# design.net
KiCad netlist of a schematic drawn in Altium Designer
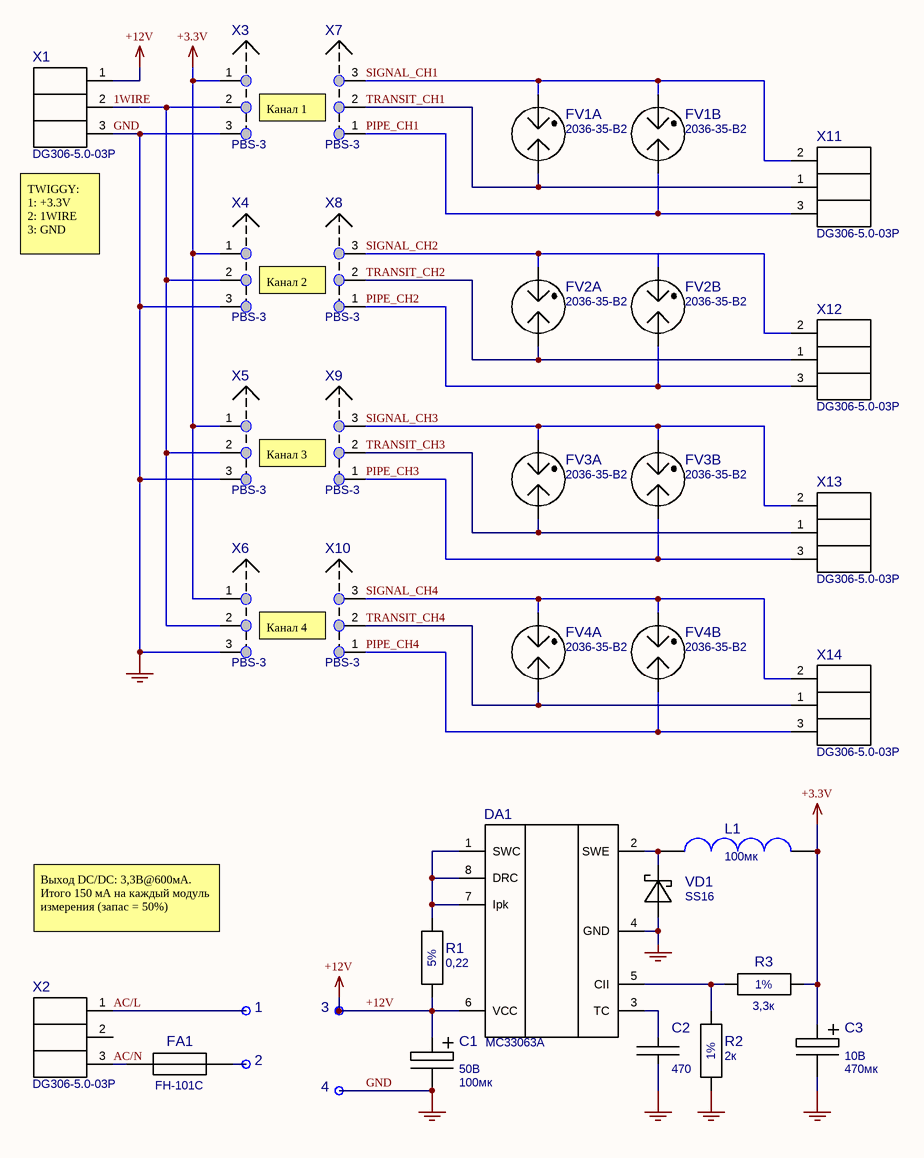
[diagram p0: Модуль соединений.SchDoc]

(export (version "E")
  (design (tool "Eeschema 10.0.6"))
  (components
    (comp (ref "1")
      (value "Plated Hole")
      (footprint "c150h100")
      (description "Single Terminal Socket")
      (fields (field (name "PART NUMBER") "PLATED_HOLE1.0_PAD1.5") (field (name "AUTHOR") "CERN DEM JLC"))
      (libsource (lib "Eletro-mechanical") (part "Single Terminal Socket"))
    )
    (comp (ref "2")
      (value "Plated Hole")
      (footprint "c150h100")
      (description "Single Terminal Socket")
      (fields (field (name "PART NUMBER") "PLATED_HOLE1.0_PAD1.5") (field (name "AUTHOR") "CERN DEM JLC"))
      (libsource (lib "Eletro-mechanical") (part "Single Terminal Socket"))
    )
    (comp (ref "3")
      (value "Plated Hole")
      (footprint "c150h100")
      (description "Single Terminal Socket")
      (fields (field (name "PART NUMBER") "PLATED_HOLE1.0_PAD1.5") (field (name "AUTHOR") "CERN DEM JLC"))
      (libsource (lib "Eletro-mechanical") (part "Single Terminal Socket"))
    )
    (comp (ref "4")
      (value "Plated Hole")
      (footprint "c150h100")
      (description "Single Terminal Socket")
      (fields (field (name "PART NUMBER") "PLATED_HOLE1.0_PAD1.5") (field (name "AUTHOR") "CERN DEM JLC"))
      (libsource (lib "Eletro-mechanical") (part "Single Terminal Socket"))
    )
    (comp (ref "C1")
      (value "100мк")
      (footprint "HITANO D08,0 H12,0 P03,5")
      (description "ECR-50 В-100 мкФ±20 %")
      (fields (field (name "VOLTAGE") "50В"))
      (libsource (lib "Калибратор") (part "ECR-50 В-100 мкФ±20 %"))
    )
    (comp (ref "C2")
      (value "470")
      (footprint "CAPC1608L")
      (description "NP0 0603-50 В-470 пФ±5 %")
      (libsource (lib "Калибратор") (part "NP0 0603-50 В-470 пФ±5 %"))
    )
    (comp (ref "C3")
      (value "470мк")
      (footprint "HITANO D08,0 H12,0 P03,5")
      (description "ECR-10 В-470 мкФ±20 %")
      (fields (field (name "VOLTAGE") "10В"))
      (libsource (lib "Калибратор") (part "ECR-10 В-470 мкФ±20 %"))
    )
    (comp (ref "DA1")
      (value "MC33063A")
      (footprint "SO-08 (150MIL)")
      (libsource (lib "Калибратор") (part "MC33063A"))
    )
    (comp (ref "FA1")
      (value "FH-101C")
      (footprint "FH-101")
      (description "FH-101")
      (libsource (lib "КОТ-С") (part "FH-101C"))
    )
    (comp (ref "FV1")
      (value "2036-35-B2")
      (footprint "2036-35-B2")
      (libsource (lib "КОТ-С") (part "2036-35-B2"))
    )
    (comp (ref "FV2")
      (value "2036-35-B2")
      (footprint "2036-35-B2")
      (libsource (lib "") (part "2036-35-B2_1"))
    )
    (comp (ref "FV3")
      (value "2036-35-B2")
      (footprint "2036-35-B2")
      (libsource (lib "") (part "2036-35-B2_1"))
    )
    (comp (ref "FV4")
      (value "2036-35-B2")
      (footprint "2036-35-B2")
      (libsource (lib "") (part "2036-35-B2_1"))
    )
    (comp (ref "L1")
      (value "100мк")
      (footprint "SDR1006")
      (description "SDR1006-101KL 100 мкГн")
      (fields
        (field (name "MANUFACTURER PART NUMBER") "SDR1006-101KL")
        (field (name "MANUFACTURER") "Bourns Inc.")
      )
      (libsource (lib "КОТ-С") (part "SDR1006-101KL 100 мкГн"))
    )
    (comp (ref "R1")
      (value "0,22")
      (footprint "RESC1608L")
      (description "0603 0,22 Ом±5 %")
      (libsource (lib "КОТ-С") (part "0603 0,22 Ом±5 %"))
    )
    (comp (ref "R2")
      (value "2к")
      (footprint "RESC1608L")
      (description "0603 10 кОм±1 %")
      (libsource (lib "КОТ-С") (part "0603 10 кОм±1 %"))
    )
    (comp (ref "R3")
      (value "3,3к")
      (footprint "RESC1608L")
      (description "0603 16 кОм±1 %")
      (libsource (lib "КОТ-С") (part "0603 16 кОм±1 %"))
    )
    (comp (ref "VD1") (value "SS16") (footprint "DO-214AC+") (libsource (lib "Калибратор") (part "SS16")))
    (comp (ref "X1")
      (value "DG306-5.0-03P")
      (footprint "DG306-5.0-03P")
      (libsource (lib "") (part "DG306-5.0-03P_1"))
    )
    (comp (ref "X2")
      (value "DG306-5.0-03P")
      (footprint "DG306-5.0-03P")
      (libsource (lib "") (part "DG306-5.0-03P_1"))
    )
    (comp (ref "X3") (value "PBS-3") (footprint "PBS-3") (libsource (lib "") (part "PBS-3_1")))
    (comp (ref "X4") (value "PBS-3") (footprint "PBS-3") (libsource (lib "") (part "PBS-3_1")))
    (comp (ref "X5") (value "PBS-3") (footprint "PBS-3") (libsource (lib "") (part "PBS-3_1")))
    (comp (ref "X6") (value "PBS-3") (footprint "PBS-3") (libsource (lib "") (part "PBS-3_1")))
    (comp (ref "X7") (value "PBS-3") (footprint "PBS-3") (libsource (lib "КОТ-С") (part "PBS-3")))
    (comp (ref "X8") (value "PBS-3") (footprint "PBS-3") (libsource (lib "КОТ-С") (part "PBS-3")))
    (comp (ref "X9") (value "PBS-3") (footprint "PBS-3") (libsource (lib "КОТ-С") (part "PBS-3")))
    (comp (ref "X10") (value "PBS-3") (footprint "PBS-3") (libsource (lib "КОТ-С") (part "PBS-3")))
    (comp (ref "X11")
      (value "DG306-5.0-03P")
      (footprint "DG306-5.0-03P")
      (libsource (lib "КОТ-С") (part "DG306-5.0-03P"))
    )
    (comp (ref "X12")
      (value "DG306-5.0-03P")
      (footprint "DG306-5.0-03P")
      (libsource (lib "КОТ-С") (part "DG306-5.0-03P"))
    )
    (comp (ref "X13")
      (value "DG306-5.0-03P")
      (footprint "DG306-5.0-03P")
      (libsource (lib "КОТ-С") (part "DG306-5.0-03P"))
    )
    (comp (ref "X14")
      (value "DG306-5.0-03P")
      (footprint "DG306-5.0-03P")
      (libsource (lib "КОТ-С") (part "DG306-5.0-03P"))
    )
  )
  (nets
    (net (code "1") (name "+3.3V") (class "Default")
      (node (ref "C3") (pin "1") (pintype "passive"))
      (node (ref "L1") (pin "2") (pintype "passive"))
      (node (ref "R3") (pin "2") (pintype "passive"))
      (node (ref "X3") (pin "1") (pintype "passive"))
      (node (ref "X4") (pin "1") (pintype "passive"))
      (node (ref "X5") (pin "1") (pintype "passive"))
      (node (ref "X6") (pin "1") (pintype "passive"))
    )
    (net (code "2") (name "+12V") (class "Default")
      (node (ref "3") (pin "1") (pinfunction "1_1") (pintype "bidirectional"))
      (node (ref "C1") (pin "1") (pintype "passive"))
      (node (ref "DA1") (pin "6") (pinfunction "VCC_6") (pintype "passive"))
      (node (ref "R1") (pin "1") (pintype "passive"))
      (node (ref "X1") (pin "1") (pintype "passive"))
    )
    (net (code "3") (name "/1WIRE") (class "Default")
      (node (ref "X1") (pin "2") (pintype "passive"))
      (node (ref "X3") (pin "2") (pintype "passive"))
      (node (ref "X4") (pin "2") (pintype "passive"))
      (node (ref "X5") (pin "2") (pintype "passive"))
      (node (ref "X6") (pin "2") (pintype "passive"))
    )
    (net (code "4") (name "/AC{slash}L") (class "Default")
      (node (ref "1") (pin "1") (pinfunction "1_1") (pintype "bidirectional"))
      (node (ref "X2") (pin "1") (pintype "passive"))
    )
    (net (code "5") (name "/AC{slash}N") (class "Default")
      (node (ref "FA1") (pin "1") (pintype "passive"))
      (node (ref "X2") (pin "3") (pintype "passive"))
    )
    (net (code "6") (name "/PIPE_CH1") (class "Default")
      (node (ref "FV1") (pin "3") (pintype "passive"))
      (node (ref "X11") (pin "3") (pintype "passive"))
      (node (ref "X7") (pin "1") (pintype "passive"))
    )
    (net (code "7") (name "/PIPE_CH2") (class "Default")
      (node (ref "FV2") (pin "3") (pintype "passive"))
      (node (ref "X12") (pin "3") (pintype "passive"))
      (node (ref "X8") (pin "1") (pintype "passive"))
    )
    (net (code "8") (name "/PIPE_CH3") (class "Default")
      (node (ref "FV3") (pin "3") (pintype "passive"))
      (node (ref "X13") (pin "3") (pintype "passive"))
      (node (ref "X9") (pin "1") (pintype "passive"))
    )
    (net (code "9") (name "/PIPE_CH4") (class "Default")
      (node (ref "FV4") (pin "3") (pintype "passive"))
      (node (ref "X10") (pin "1") (pintype "passive"))
      (node (ref "X14") (pin "3") (pintype "passive"))
    )
    (net (code "10") (name "/SIGNAL_CH1") (class "Default")
      (node (ref "FV1") (pin "2") (pintype "passive"))
      (node (ref "X11") (pin "2") (pintype "passive"))
      (node (ref "X7") (pin "3") (pintype "passive"))
    )
    (net (code "11") (name "/SIGNAL_CH2") (class "Default")
      (node (ref "FV2") (pin "2") (pintype "passive"))
      (node (ref "X12") (pin "2") (pintype "passive"))
      (node (ref "X8") (pin "3") (pintype "passive"))
    )
    (net (code "12") (name "/SIGNAL_CH3") (class "Default")
      (node (ref "FV3") (pin "2") (pintype "passive"))
      (node (ref "X13") (pin "2") (pintype "passive"))
      (node (ref "X9") (pin "3") (pintype "passive"))
    )
    (net (code "13") (name "/SIGNAL_CH4") (class "Default")
      (node (ref "FV4") (pin "2") (pintype "passive"))
      (node (ref "X10") (pin "3") (pintype "passive"))
      (node (ref "X14") (pin "2") (pintype "passive"))
    )
    (net (code "14") (name "/TRANSIT_CH1") (class "Default")
      (node (ref "FV1") (pin "1") (pintype "passive"))
      (node (ref "X11") (pin "1") (pintype "passive"))
      (node (ref "X7") (pin "2") (pintype "passive"))
    )
    (net (code "15") (name "/TRANSIT_CH2") (class "Default")
      (node (ref "FV2") (pin "1") (pintype "passive"))
      (node (ref "X12") (pin "1") (pintype "passive"))
      (node (ref "X8") (pin "2") (pintype "passive"))
    )
    (net (code "16") (name "/TRANSIT_CH3") (class "Default")
      (node (ref "FV3") (pin "1") (pintype "passive"))
      (node (ref "X13") (pin "1") (pintype "passive"))
      (node (ref "X9") (pin "2") (pintype "passive"))
    )
    (net (code "17") (name "/TRANSIT_CH4") (class "Default")
      (node (ref "FV4") (pin "1") (pintype "passive"))
      (node (ref "X10") (pin "2") (pintype "passive"))
      (node (ref "X14") (pin "1") (pintype "passive"))
    )
    (net (code "18") (name "GND") (class "Default")
      (node (ref "4") (pin "1") (pinfunction "1_1") (pintype "bidirectional"))
      (node (ref "C1") (pin "2") (pintype "passive"))
      (node (ref "C2") (pin "1") (pintype "passive"))
      (node (ref "C3") (pin "2") (pintype "passive"))
      (node (ref "DA1") (pin "4") (pinfunction "GND_4") (pintype "passive"))
      (node (ref "R2") (pin "1") (pintype "passive"))
      (node (ref "VD1") (pin "1") (pintype "passive"))
      (node (ref "X1") (pin "3") (pintype "passive"))
      (node (ref "X3") (pin "3") (pintype "passive"))
      (node (ref "X4") (pin "3") (pintype "passive"))
      (node (ref "X5") (pin "3") (pintype "passive"))
      (node (ref "X6") (pin "3") (pintype "passive"))
    )
    (net (code "19") (name "Net-(2-Pad1)") (class "Default")
      (node (ref "2") (pin "1") (pinfunction "1_1") (pintype "bidirectional"))
      (node (ref "FA1") (pin "2") (pintype "passive"))
    )
    (net (code "20") (name "Net-(DA1-CII)") (class "Default")
      (node (ref "DA1") (pin "5") (pinfunction "CII_5") (pintype "passive"))
      (node (ref "R2") (pin "2") (pintype "passive"))
      (node (ref "R3") (pin "1") (pintype "passive"))
    )
    (net (code "21") (name "Net-(DA1-DRC)") (class "Default")
      (node (ref "DA1") (pin "1") (pinfunction "SWC_1") (pintype "passive"))
      (node (ref "DA1") (pin "7") (pinfunction "Ipk_7") (pintype "passive"))
      (node (ref "DA1") (pin "8") (pinfunction "DRC_8") (pintype "passive"))
      (node (ref "R1") (pin "2") (pintype "passive"))
    )
    (net (code "22") (name "Net-(DA1-SWE)") (class "Default")
      (node (ref "DA1") (pin "2") (pinfunction "SWE_2") (pintype "passive"))
      (node (ref "L1") (pin "1") (pintype "passive"))
      (node (ref "VD1") (pin "2") (pintype "passive"))
    )
    (net (code "23") (name "Net-(DA1-TC)") (class "Default")
      (node (ref "C2") (pin "2") (pintype "passive"))
      (node (ref "DA1") (pin "3") (pinfunction "TC_3") (pintype "passive"))
    )
    (net (code "24") (name "unconnected-(X2-Pad2)") (class "Default")
      (node (ref "X2") (pin "2") (pintype "passive"))
    )
  )
)
